# reguladores.net
KiCad netlist of a schematic drawn in EAGLE
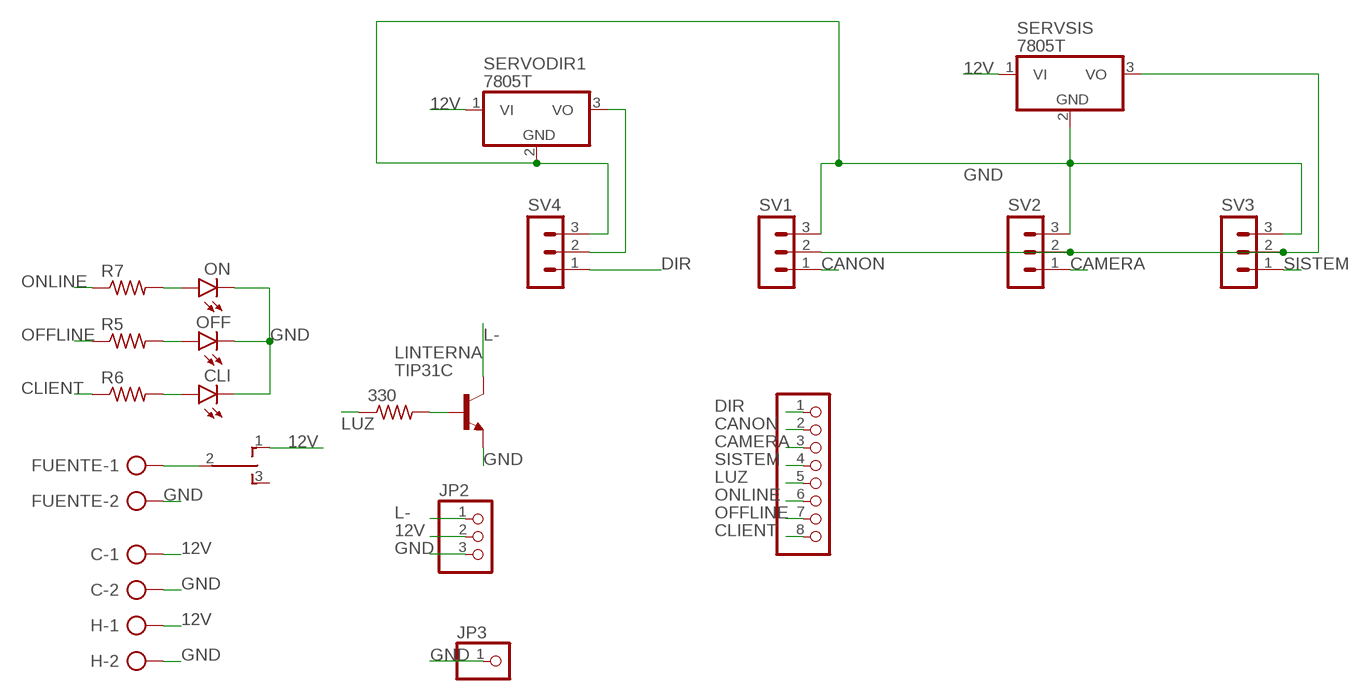
[diagram p0: schematic, sheet 1]

(export (version "E")
  (design (tool "Eeschema 10.0.6"))
  (components
    (comp (ref "330")
      (value "R-US_0204/7")
      (footprint "eagle-import:0204_7")
      (libsource (lib "eagle-import") (part "R-US_0204/7"))
    )
    (comp (ref "C")
      (value "AK500/2-H")
      (footprint "eagle-import:AK500_2-H")
      (libsource (lib "eagle-import") (part "AK500/2-H"))
    )
    (comp (ref "CLI")
      (value "LED5MM")
      (footprint "eagle-import:LED5MM")
      (libsource (lib "eagle-import") (part "LED5MM"))
    )
    (comp (ref "FUENTE")
      (value "AK500/2-H")
      (footprint "eagle-import:AK500_2-H")
      (libsource (lib "eagle-import") (part "AK500/2-H"))
    )
    (comp (ref "H")
      (value "AK500/2-H")
      (footprint "eagle-import:AK500_2-H")
      (libsource (lib "eagle-import") (part "AK500/2-H"))
    )
    (comp (ref "JP1")
      (value "PINHD-1X8")
      (footprint "eagle-import:1X08")
      (libsource (lib "eagle-import") (part "PINHD-1X8"))
    )
    (comp (ref "JP2")
      (value "PINHD-1X3")
      (footprint "eagle-import:1X03")
      (libsource (lib "eagle-import") (part "PINHD-1X3"))
    )
    (comp (ref "JP3")
      (value "PINHD-1X1")
      (footprint "eagle-import:1X01")
      (libsource (lib "eagle-import") (part "PINHD-1X1"))
    )
    (comp (ref "LINTERNA")
      (value "TIP31C")
      (footprint "eagle-import:TO220")
      (libsource (lib "eagle-import") (part "TIP31C"))
    )
    (comp (ref "OFF")
      (value "LED5MM")
      (footprint "eagle-import:LED5MM")
      (libsource (lib "eagle-import") (part "LED5MM"))
    )
    (comp (ref "ON")
      (value "LED5MM")
      (footprint "eagle-import:LED5MM")
      (libsource (lib "eagle-import") (part "LED5MM"))
    )
    (comp (ref "R5")
      (value "R-US_0204/7")
      (footprint "eagle-import:0204_7")
      (libsource (lib "eagle-import") (part "R-US_0204/7"))
    )
    (comp (ref "R6")
      (value "R-US_0204/7")
      (footprint "eagle-import:0204_7")
      (libsource (lib "eagle-import") (part "R-US_0204/7"))
    )
    (comp (ref "R7")
      (value "R-US_0204/7")
      (footprint "eagle-import:0204_7")
      (libsource (lib "eagle-import") (part "R-US_0204/7"))
    )
    (comp (ref "S1")
      (value "TL39WO")
      (footprint "eagle-import:TL3XWO")
      (libsource (lib "eagle-import") (part "TL39WO"))
    )
    (comp (ref "SERVODIR1")
      (value "7805T")
      (footprint "eagle-import:TO220H")
      (libsource (lib "eagle-import") (part "78T05"))
    )
    (comp (ref "SERVSIS")
      (value "7805T")
      (footprint "eagle-import:TO220H")
      (libsource (lib "eagle-import") (part "78T05"))
    )
    (comp (ref "SV1")
      (value "MA03-1")
      (footprint "eagle-import:MA03-1")
      (libsource (lib "eagle-import") (part "MA03-1"))
    )
    (comp (ref "SV2")
      (value "MA03-1")
      (footprint "eagle-import:MA03-1")
      (libsource (lib "eagle-import") (part "MA03-1"))
    )
    (comp (ref "SV3")
      (value "MA03-1")
      (footprint "eagle-import:MA03-1")
      (libsource (lib "eagle-import") (part "MA03-1"))
    )
    (comp (ref "SV4")
      (value "MA03-1")
      (footprint "eagle-import:MA03-1")
      (libsource (lib "eagle-import") (part "MA03-1"))
    )
  )
  (nets
    (net (code "1") (name "/12V") (class "Default")
      (node (ref "C") (pin "1") (pinfunction "KL_1") (pintype "passive"))
      (node (ref "H") (pin "1") (pinfunction "KL_1") (pintype "passive"))
      (node (ref "JP2") (pin "2") (pinfunction "2_2") (pintype "passive"))
      (node (ref "S1") (pin "1") (pinfunction "O_1") (pintype "passive"))
      (node (ref "SERVODIR1") (pin "1") (pinfunction "VI_1") (pintype "input"))
      (node (ref "SERVSIS") (pin "1") (pinfunction "VI_1") (pintype "input"))
    )
    (net (code "2") (name "/CAMERA") (class "Default")
      (node (ref "JP1") (pin "3") (pinfunction "3_3") (pintype "passive"))
      (node (ref "SV2") (pin "1") (pinfunction "1_1") (pintype "passive"))
    )
    (net (code "3") (name "/CANON") (class "Default")
      (node (ref "JP1") (pin "2") (pinfunction "2_2") (pintype "passive"))
      (node (ref "SV1") (pin "1") (pinfunction "1_1") (pintype "passive"))
    )
    (net (code "4") (name "/CLIENT") (class "Default")
      (node (ref "JP1") (pin "8") (pinfunction "8_8") (pintype "passive"))
      (node (ref "R6") (pin "1") (pinfunction "1_1") (pintype "passive"))
    )
    (net (code "5") (name "/DIR") (class "Default")
      (node (ref "JP1") (pin "1") (pinfunction "1_1") (pintype "passive"))
      (node (ref "SV4") (pin "1") (pinfunction "1_1") (pintype "passive"))
    )
    (net (code "6") (name "/GND") (class "Default")
      (node (ref "C") (pin "2") (pinfunction "KL_2") (pintype "passive"))
      (node (ref "CLI") (pin "K") (pinfunction "C_K") (pintype "passive"))
      (node (ref "FUENTE") (pin "2") (pinfunction "KL_2") (pintype "passive"))
      (node (ref "H") (pin "2") (pinfunction "KL_2") (pintype "passive"))
      (node (ref "JP2") (pin "3") (pinfunction "3_3") (pintype "passive"))
      (node (ref "JP3") (pin "1") (pinfunction "1_1") (pintype "passive"))
      (node (ref "LINTERNA") (pin "3") (pinfunction "E_3") (pintype "passive"))
      (node (ref "OFF") (pin "K") (pinfunction "C_K") (pintype "passive"))
      (node (ref "ON") (pin "K") (pinfunction "C_K") (pintype "passive"))
      (node (ref "SERVODIR1") (pin "2") (pinfunction "GND_2") (pintype "passive"))
      (node (ref "SERVSIS") (pin "2") (pinfunction "GND_2") (pintype "passive"))
      (node (ref "SV1") (pin "3") (pinfunction "3_3") (pintype "passive"))
      (node (ref "SV2") (pin "3") (pinfunction "3_3") (pintype "passive"))
      (node (ref "SV3") (pin "3") (pinfunction "3_3") (pintype "passive"))
      (node (ref "SV4") (pin "3") (pinfunction "3_3") (pintype "passive"))
    )
    (net (code "7") (name "/L-") (class "Default")
      (node (ref "JP2") (pin "1") (pinfunction "1_1") (pintype "passive"))
      (node (ref "LINTERNA") (pin "2") (pinfunction "C_2") (pintype "passive"))
    )
    (net (code "8") (name "/LUZ") (class "Default")
      (node (ref "330") (pin "1") (pinfunction "1_1") (pintype "passive"))
      (node (ref "JP1") (pin "5") (pinfunction "5_5") (pintype "passive"))
    )
    (net (code "9") (name "/OFFLINE") (class "Default")
      (node (ref "JP1") (pin "7") (pinfunction "7_7") (pintype "passive"))
      (node (ref "R5") (pin "1") (pinfunction "1_1") (pintype "passive"))
    )
    (net (code "10") (name "/ONLINE") (class "Default")
      (node (ref "JP1") (pin "6") (pinfunction "6_6") (pintype "passive"))
      (node (ref "R7") (pin "1") (pinfunction "1_1") (pintype "passive"))
    )
    (net (code "11") (name "/SISTEM") (class "Default")
      (node (ref "JP1") (pin "4") (pinfunction "4_4") (pintype "passive"))
      (node (ref "SV3") (pin "1") (pinfunction "1_1") (pintype "passive"))
    )
    (net (code "12") (name "Net-(CLI-PadA)") (class "Default")
      (node (ref "CLI") (pin "A") (pinfunction "A_A") (pintype "passive"))
      (node (ref "R6") (pin "2") (pinfunction "2_2") (pintype "passive"))
    )
    (net (code "13") (name "Net-(FUENTEA-KL)") (class "Default")
      (node (ref "FUENTE") (pin "1") (pinfunction "KL_1") (pintype "passive"))
      (node (ref "S1") (pin "2") (pinfunction "P_2") (pintype "passive"))
    )
    (net (code "14") (name "Net-(LINTERNA-B)") (class "Default")
      (node (ref "330") (pin "2") (pinfunction "2_2") (pintype "passive"))
      (node (ref "LINTERNA") (pin "1") (pinfunction "B_1") (pintype "passive"))
    )
    (net (code "15") (name "Net-(OFF-PadA)") (class "Default")
      (node (ref "OFF") (pin "A") (pinfunction "A_A") (pintype "passive"))
      (node (ref "R5") (pin "2") (pinfunction "2_2") (pintype "passive"))
    )
    (net (code "16") (name "Net-(ON-PadA)") (class "Default")
      (node (ref "ON") (pin "A") (pinfunction "A_A") (pintype "passive"))
      (node (ref "R7") (pin "2") (pinfunction "2_2") (pintype "passive"))
    )
    (net (code "17") (name "Net-(SERVODIR1-VO)") (class "Default")
      (node (ref "SERVODIR1") (pin "3") (pinfunction "VO_3") (pintype "passive"))
      (node (ref "SV4") (pin "2") (pinfunction "2_2") (pintype "passive"))
    )
    (net (code "18") (name "Net-(SERVSIS-VO)") (class "Default")
      (node (ref "SERVSIS") (pin "3") (pinfunction "VO_3") (pintype "passive"))
      (node (ref "SV1") (pin "2") (pinfunction "2_2") (pintype "passive"))
      (node (ref "SV2") (pin "2") (pinfunction "2_2") (pintype "passive"))
      (node (ref "SV3") (pin "2") (pinfunction "2_2") (pintype "passive"))
    )
    (net (code "19") (name "unconnected-(S1-S-Pad3)") (class "Default")
      (node (ref "S1") (pin "3") (pinfunction "S_3") (pintype "passive"))
    )
  )
)
